# MT6631.net
KiCad netlist of a schematic drawn in Altium Designer
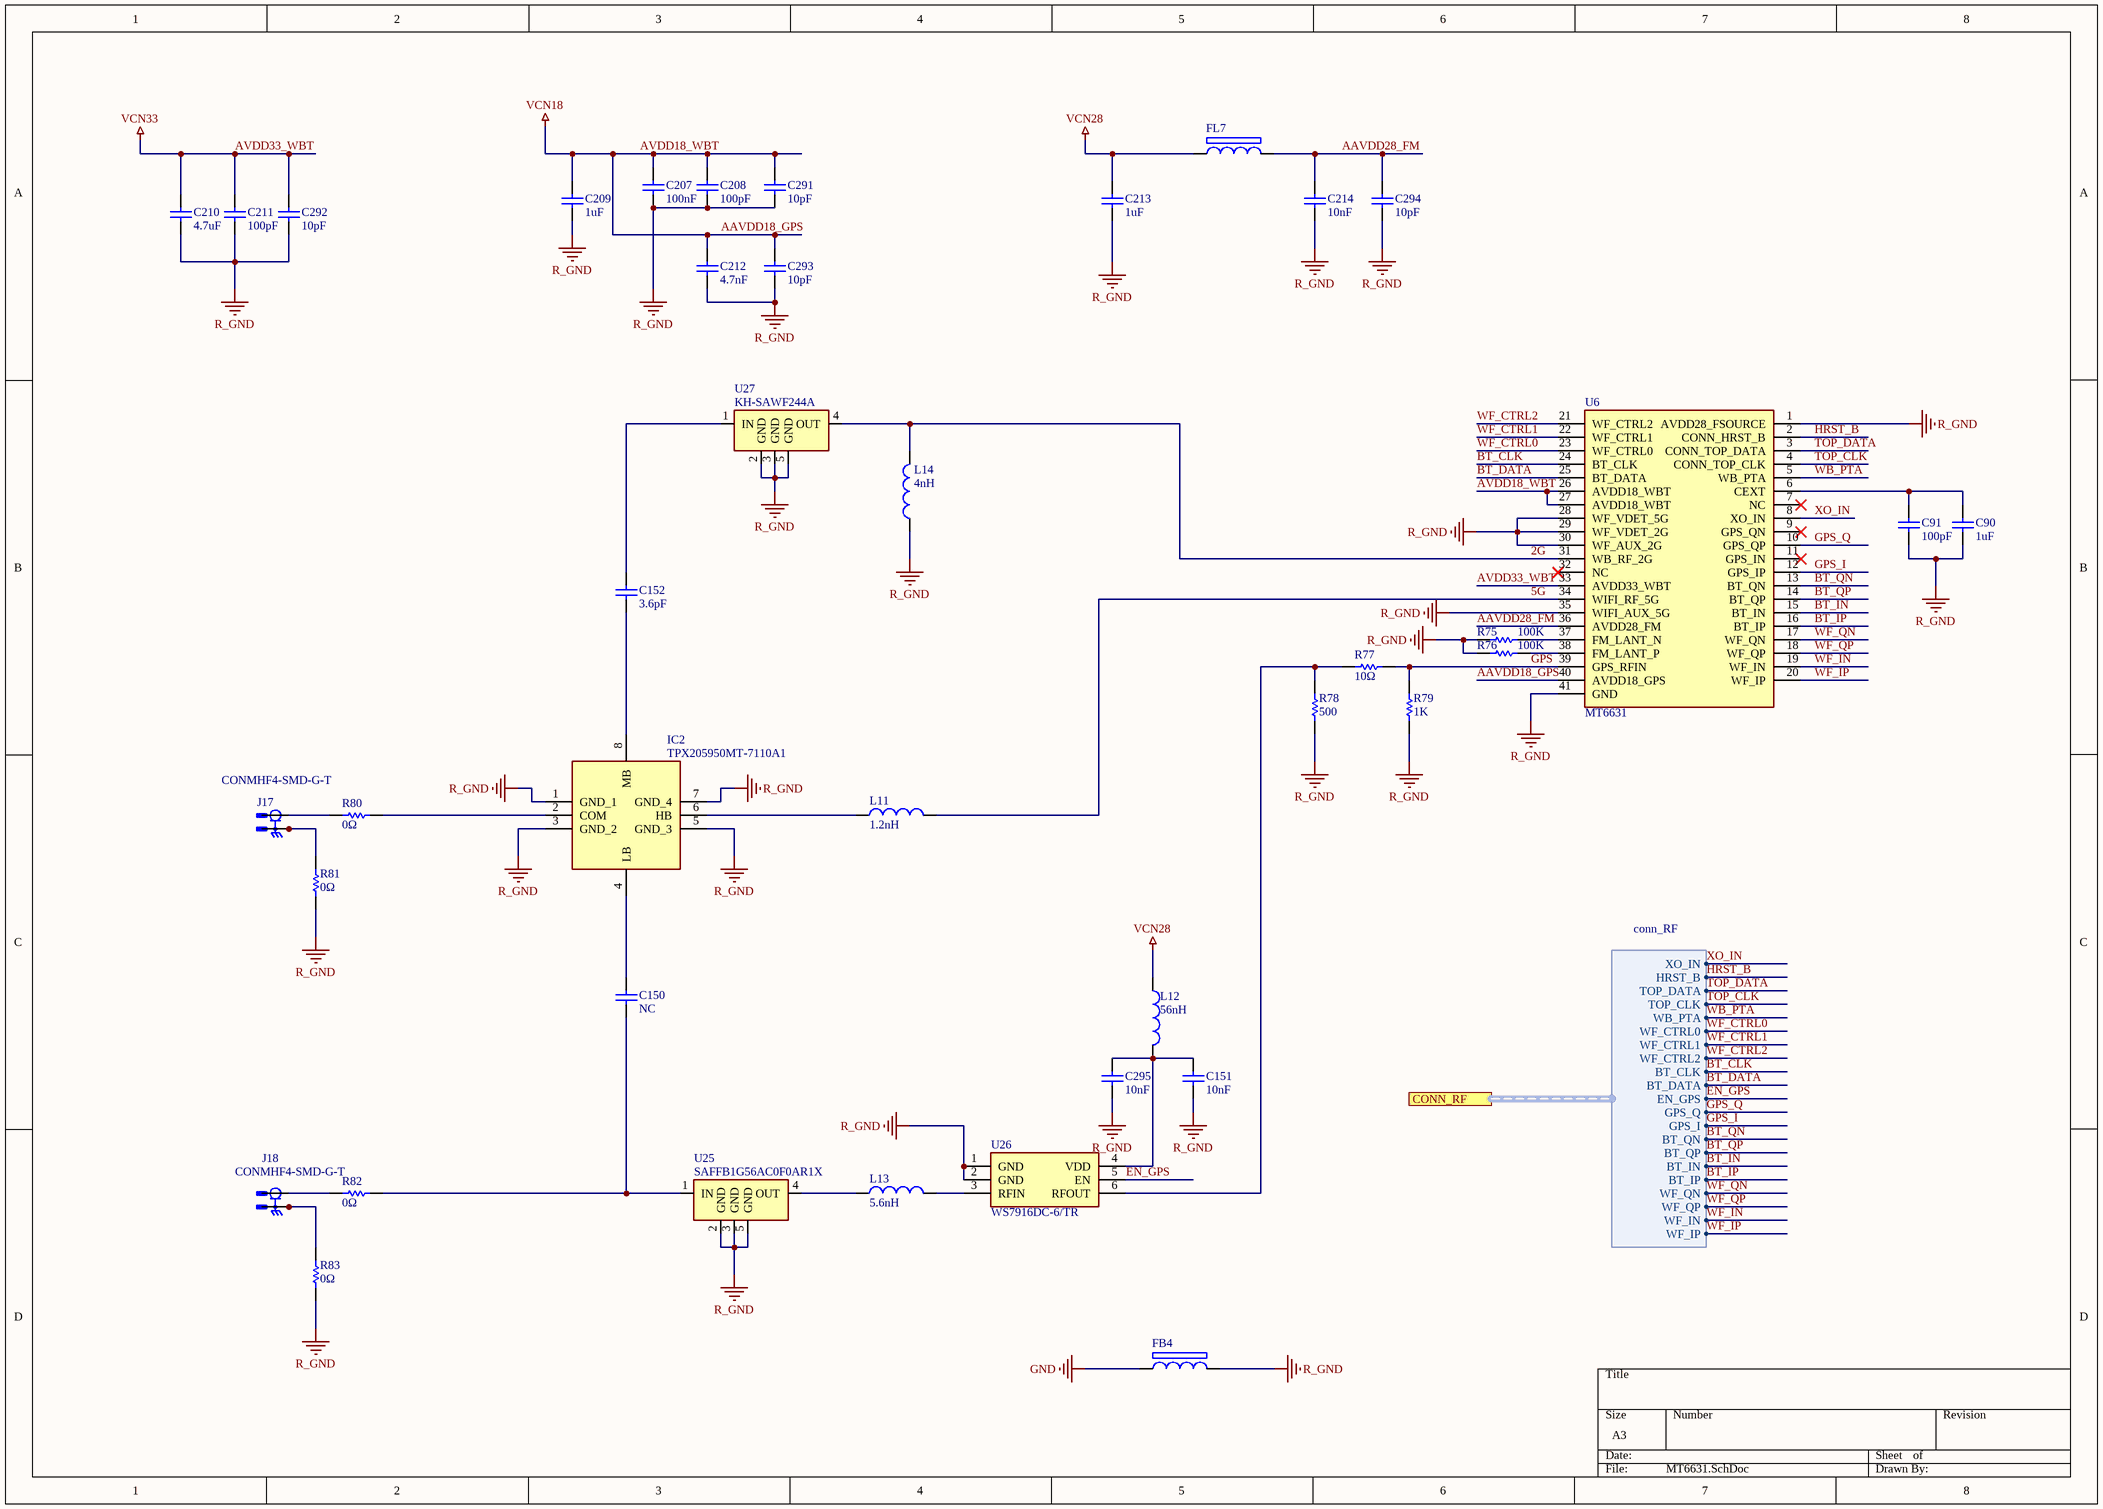
[diagram p0: MT6631.SchDoc]

(export (version "E")
  (design (tool "Eeschema 10.0.6"))
  (components
    (comp (ref "C90")
      (value "1uF")
      (footprint "C0805")
      (fields (field (name "Comment") "C0805"))
      (libsource (lib "kit") (part "C0805"))
    )
    (comp (ref "C91")
      (value "100pF")
      (footprint "C0402")
      (fields (field (name "Comment") "C0402"))
      (libsource (lib "kit") (part "C0402"))
    )
    (comp (ref "C150")
      (value "NC")
      (footprint "C0402")
      (fields (field (name "Comment") "C0402"))
      (libsource (lib "kit") (part "C0402"))
    )
    (comp (ref "C151")
      (value "10nF")
      (footprint "C0603")
      (fields (field (name "Comment") "C0603"))
      (libsource (lib "kit") (part "C0603"))
    )
    (comp (ref "C152")
      (value "3.6pF")
      (footprint "C0402")
      (fields (field (name "Comment") "C0402"))
      (libsource (lib "kit") (part "C0402"))
    )
    (comp (ref "C207")
      (value "100nF")
      (footprint "C0603")
      (fields (field (name "Comment") "C0603"))
      (libsource (lib "kit") (part "C0603"))
    )
    (comp (ref "C208")
      (value "100pF")
      (footprint "C0402")
      (fields (field (name "Comment") "C0402"))
      (libsource (lib "kit") (part "C0402"))
    )
    (comp (ref "C209")
      (value "1uF")
      (footprint "C0805")
      (fields (field (name "Comment") "C0805"))
      (libsource (lib "kit") (part "C0805"))
    )
    (comp (ref "C210")
      (value "4.7uF")
      (footprint "C0805")
      (fields (field (name "Comment") "C0805"))
      (libsource (lib "kit") (part "C0805"))
    )
    (comp (ref "C211")
      (value "100pF")
      (footprint "C0402")
      (fields (field (name "Comment") "C0402"))
      (libsource (lib "kit") (part "C0402"))
    )
    (comp (ref "C212")
      (value "4.7nF")
      (footprint "C0603")
      (fields (field (name "Comment") "C0603"))
      (libsource (lib "kit") (part "C0603"))
    )
    (comp (ref "C213")
      (value "1uF")
      (footprint "C0805")
      (fields (field (name "Comment") "C0805"))
      (libsource (lib "kit") (part "C0805"))
    )
    (comp (ref "C214")
      (value "10nF")
      (footprint "C0603")
      (fields (field (name "Comment") "C0603"))
      (libsource (lib "kit") (part "C0603"))
    )
    (comp (ref "C291")
      (value "10pF")
      (footprint "C0402")
      (fields (field (name "Comment") "C0402"))
      (libsource (lib "kit") (part "C0402"))
    )
    (comp (ref "C292")
      (value "10pF")
      (footprint "C0402")
      (fields (field (name "Comment") "C0402"))
      (libsource (lib "kit") (part "C0402"))
    )
    (comp (ref "C293")
      (value "10pF")
      (footprint "C0402")
      (fields (field (name "Comment") "C0402"))
      (libsource (lib "kit") (part "C0402"))
    )
    (comp (ref "C294")
      (value "10pF")
      (footprint "C0402")
      (fields (field (name "Comment") "C0402"))
      (libsource (lib "kit") (part "C0402"))
    )
    (comp (ref "C295")
      (value "10nF")
      (footprint "C0603")
      (fields (field (name "Comment") "C0603"))
      (libsource (lib "kit") (part "C0603"))
    )
    (comp (ref "FB4")
      (value "BLM18KG121TN1D")
      (footprint "BLM18EG101TH1D")
      (description "Ferrite Bead. 0603. 3A.  DC Resistance(DCR) 30mΩ. 120Ω@100MHz")
      (fields (field (name "MOUSER PART NUMBER") "81-BLM18KG121TN1D"))
      (libsource (lib "kit") (part "BLM18KG121TN1D"))
    )
    (comp (ref "FL7")
      (value "BLM18BD252SN1D")
      (footprint "BEADC1608X95N")
      (description "Inductor Chip Bead 2.5KOhm 25% 100MHz Ferrite 50mA 0603")
      (libsource (lib "kit") (part "BLM18BD252SN1D"))
    )
    (comp (ref "IC2")
      (value "TPX205950MT-7110A1")
      (footprint "TPX205950MT7110A1")
      (description "wifi, bluetooth, GPS. 2.4GHz, 5GHz, 1.6GHz")
      (fields (field (name "MOUSER PART NUMBER") "810-TPX20595MT7110A1"))
      (libsource (lib "kit") (part "TPX205950MT-7110A1"))
    )
    (comp (ref "J17")
      (value "CONMHF4-SMD-G-T")
      (footprint "LINX_CONMHF4-SMD-G-T")
      (description "MHF4 Jack 50 Ohm PCB Surface Mount")
      (libsource (lib "kit") (part "CONMHF4-SMD-G-T"))
    )
    (comp (ref "J18")
      (value "CONMHF4-SMD-G-T")
      (footprint "LINX_CONMHF4-SMD-G-T")
      (description "MHF4 Jack 50 Ohm PCB Surface Mount")
      (libsource (lib "kit") (part "CONMHF4-SMD-G-T"))
    )
    (comp (ref "L11")
      (value "1.2nH")
      (footprint "L0402")
      (fields (field (name "Comment") "L0402"))
      (libsource (lib "kit") (part "L0402"))
    )
    (comp (ref "L12")
      (value "56nH")
      (footprint "L0402")
      (fields (field (name "Comment") "L0402"))
      (libsource (lib "kit") (part "L0402"))
    )
    (comp (ref "L13")
      (value "5.6nH")
      (footprint "L0402")
      (fields (field (name "Comment") "L0402"))
      (libsource (lib "kit") (part "L0402"))
    )
    (comp (ref "L14")
      (value "4nH")
      (footprint "L0402")
      (fields (field (name "Comment") "L0402"))
      (libsource (lib "kit") (part "L0402"))
    )
    (comp (ref "R75")
      (value "100K")
      (footprint "R0603")
      (fields (field (name "Comment") "R0603"))
      (libsource (lib "kit") (part "R0603"))
    )
    (comp (ref "R76")
      (value "100K")
      (footprint "R0603")
      (fields (field (name "Comment") "R0603"))
      (libsource (lib "kit") (part "R0603"))
    )
    (comp (ref "R77")
      (value "10Ω")
      (footprint "R0603")
      (fields (field (name "Comment") "R0603"))
      (libsource (lib "kit") (part "R0603"))
    )
    (comp (ref "R78")
      (value "500")
      (footprint "R0603")
      (fields (field (name "Comment") "R0603"))
      (libsource (lib "kit") (part "R0603"))
    )
    (comp (ref "R79")
      (value "1K")
      (footprint "R0603")
      (fields (field (name "Comment") "R0603"))
      (libsource (lib "kit") (part "R0603"))
    )
    (comp (ref "R80")
      (value "0Ω")
      (footprint "R0603")
      (fields (field (name "Comment") "R0603"))
      (libsource (lib "kit") (part "R0603"))
    )
    (comp (ref "R81")
      (value "0Ω")
      (footprint "R0603")
      (fields (field (name "Comment") "R0603"))
      (libsource (lib "kit") (part "R0603"))
    )
    (comp (ref "R82")
      (value "0Ω")
      (footprint "R0603")
      (fields (field (name "Comment") "R0603"))
      (libsource (lib "kit") (part "R0603"))
    )
    (comp (ref "R83")
      (value "0Ω")
      (footprint "R0603")
      (fields (field (name "Comment") "R0603"))
      (libsource (lib "kit") (part "R0603"))
    )
    (comp (ref "U6") (value "MT6631") (footprint "MT6631") (libsource (lib "kit") (part "MT6631")))
    (comp (ref "U25")
      (value "SAFFB1G56AC0F0AR1X")
      (footprint "SAFFB1G56AC0F0AR1X")
      (description "lọc thông giải GPS")
      (libsource (lib "kit") (part "SAFFB1G56AC0F0AR1X"))
    )
    (comp (ref "U26")
      (value "WS7916DC-6/TR")
      (footprint "WS7916DC-6/TR")
      (description "khuếch đại tín hiệu GPS")
      (libsource (lib "kit") (part "WS7916DC-6/TR"))
    )
    (comp (ref "U27")
      (value "KH-SAWF244A")
      (footprint "KH-SAWF244A")
      (description "bộ lọc thông dải 2.4GHz")
      (libsource (lib "kit") (part "KH-SAWF244A"))
    )
  )
  (nets
    (net (code "2") (name "/2G") (class "Default")
      (node (ref "L14") (pin "2") (pinfunction "2_2") (pintype "passive"))
      (node (ref "U27") (pin "4") (pinfunction "OUT_4") (pintype "power_in"))
      (node (ref "U6") (pin "31") (pinfunction "WB_RF_2G_31") (pintype "passive"))
    )
    (net (code "3") (name "/5G") (class "Default")
      (node (ref "L11") (pin "2") (pinfunction "2_2") (pintype "passive"))
      (node (ref "U6") (pin "34") (pinfunction "WIFI_RF_5G_34") (pintype "passive"))
    )
    (net (code "4") (name "/AAVDD28_FM") (class "Default")
      (node (ref "C214") (pin "2") (pinfunction "2_2") (pintype "passive"))
      (node (ref "C294") (pin "2") (pinfunction "2_2") (pintype "passive"))
      (node (ref "FL7") (pin "2") (pinfunction "2_2") (pintype "passive"))
      (node (ref "U6") (pin "36") (pinfunction "AVDD28_FM_36") (pintype "passive"))
    )
    (net (code "5") (name "/BT_CLK") (class "Default")
      (node (ref "U6") (pin "24") (pinfunction "BT_CLK_24") (pintype "passive"))
    )
    (net (code "6") (name "/BT_DATA") (class "Default")
      (node (ref "U6") (pin "25") (pinfunction "BT_DATA_25") (pintype "passive"))
    )
    (net (code "7") (name "/BT_IN") (class "Default")
      (node (ref "U6") (pin "15") (pinfunction "BT_IN_15") (pintype "passive"))
    )
    (net (code "8") (name "/BT_IP") (class "Default")
      (node (ref "U6") (pin "16") (pinfunction "BT_IP_16") (pintype "passive"))
    )
    (net (code "9") (name "/BT_QN") (class "Default")
      (node (ref "U6") (pin "13") (pinfunction "BT_QN_13") (pintype "passive"))
    )
    (net (code "10") (name "/BT_QP") (class "Default")
      (node (ref "U6") (pin "14") (pinfunction "BT_QP_14") (pintype "passive"))
    )
    (net (code "11") (name "/EN_GPS") (class "Default")
      (node (ref "U26") (pin "5") (pinfunction "EN_5") (pintype "passive"))
    )
    (net (code "12") (name "/GPS") (class "Default")
      (node (ref "R77") (pin "2") (pinfunction "2_2") (pintype "passive"))
      (node (ref "R79") (pin "2") (pinfunction "2_2") (pintype "passive"))
      (node (ref "U6") (pin "39") (pinfunction "GPS_RFIN_39") (pintype "passive"))
    )
    (net (code "13") (name "/GPS_I") (class "Default")
      (node (ref "U6") (pin "12") (pinfunction "GPS_IP_12") (pintype "passive"))
    )
    (net (code "14") (name "/GPS_Q") (class "Default")
      (node (ref "U6") (pin "10") (pinfunction "GPS_QP_10") (pintype "passive"))
    )
    (net (code "15") (name "/HRST_B") (class "Default")
      (node (ref "U6") (pin "2") (pinfunction "CONN_HRST_B_2") (pintype "passive"))
    )
    (net (code "16") (name "/TOP_CLK") (class "Default")
      (node (ref "U6") (pin "4") (pinfunction "CONN_TOP_CLK_4") (pintype "passive"))
    )
    (net (code "17") (name "/TOP_DATA") (class "Default")
      (node (ref "U6") (pin "3") (pinfunction "CONN_TOP_DATA_3") (pintype "passive"))
    )
    (net (code "18") (name "/WB_PTA") (class "Default")
      (node (ref "U6") (pin "5") (pinfunction "WB_PTA_5") (pintype "passive"))
    )
    (net (code "19") (name "/WF_CTRL0") (class "Default")
      (node (ref "U6") (pin "23") (pinfunction "WF_CTRL0_23") (pintype "passive"))
    )
    (net (code "20") (name "/WF_CTRL1") (class "Default")
      (node (ref "U6") (pin "22") (pinfunction "WF_CTRL1_22") (pintype "passive"))
    )
    (net (code "21") (name "/WF_CTRL2") (class "Default")
      (node (ref "U6") (pin "21") (pinfunction "WF_CTRL2_21") (pintype "passive"))
    )
    (net (code "22") (name "/WF_IN") (class "Default")
      (node (ref "U6") (pin "19") (pinfunction "WF_IN_19") (pintype "passive"))
    )
    (net (code "23") (name "/WF_IP") (class "Default")
      (node (ref "U6") (pin "20") (pinfunction "WF_IP_20") (pintype "passive"))
    )
    (net (code "24") (name "/WF_QN") (class "Default")
      (node (ref "U6") (pin "17") (pinfunction "WF_QN_17") (pintype "passive"))
    )
    (net (code "25") (name "/WF_QP") (class "Default")
      (node (ref "U6") (pin "18") (pinfunction "WF_QP_18") (pintype "passive"))
    )
    (net (code "26") (name "/XO_IN") (class "Default")
      (node (ref "U6") (pin "8") (pinfunction "XO_IN_8") (pintype "passive"))
    )
    (net (code "28") (name "GND") (class "Default")
      (node (ref "FB4") (pin "1") (pinfunction "1_1") (pintype "passive"))
    )
    (net (code "29") (name "Net-(IC2-COM)") (class "Default")
      (node (ref "IC2") (pin "2") (pinfunction "COM_2") (pintype "passive"))
      (node (ref "R80") (pin "2") (pinfunction "2_2") (pintype "passive"))
    )
    (net (code "30") (name "Net-(IC2-HB)") (class "Default")
      (node (ref "IC2") (pin "6") (pinfunction "HB_6") (pintype "passive"))
      (node (ref "L11") (pin "1") (pinfunction "1_1") (pintype "passive"))
    )
    (net (code "31") (name "Net-(IC2-LB)") (class "Default")
      (node (ref "C150") (pin "2") (pinfunction "2_2") (pintype "passive"))
      (node (ref "IC2") (pin "4") (pinfunction "LB_4") (pintype "passive"))
    )
    (net (code "32") (name "Net-(IC2-MB)") (class "Default")
      (node (ref "C152") (pin "1") (pinfunction "1_1") (pintype "passive"))
      (node (ref "IC2") (pin "8") (pinfunction "MB_8") (pintype "passive"))
    )
    (net (code "33") (name "Net-(J17-2-PadS1)") (class "Default")
      (node (ref "J17") (pin "S1") (pinfunction "2_S1") (pintype "passive"))
      (node (ref "J17") (pin "S2") (pinfunction "2_S2") (pintype "passive"))
      (node (ref "J17") (pin "S3") (pinfunction "2_S3") (pintype "passive"))
      (node (ref "R81") (pin "2") (pinfunction "2_2") (pintype "passive"))
    )
    (net (code "34") (name "Net-(J17-Pad1)") (class "Default")
      (node (ref "J17") (pin "1") (pinfunction "1_1") (pintype "passive"))
      (node (ref "R80") (pin "1") (pinfunction "1_1") (pintype "passive"))
    )
    (net (code "35") (name "Net-(J18-2-PadS1)") (class "Default")
      (node (ref "J18") (pin "S1") (pinfunction "2_S1") (pintype "passive"))
      (node (ref "J18") (pin "S2") (pinfunction "2_S2") (pintype "passive"))
      (node (ref "J18") (pin "S3") (pinfunction "2_S3") (pintype "passive"))
      (node (ref "R83") (pin "2") (pinfunction "2_2") (pintype "passive"))
    )
    (net (code "36") (name "Net-(J18-Pad1)") (class "Default")
      (node (ref "J18") (pin "1") (pinfunction "1_1") (pintype "passive"))
      (node (ref "R82") (pin "1") (pinfunction "1_1") (pintype "passive"))
    )
    (net (code "37") (name "Net-(U6-CEXT)") (class "Default")
      (node (ref "C90") (pin "2") (pinfunction "2_2") (pintype "passive"))
      (node (ref "C91") (pin "2") (pinfunction "2_2") (pintype "passive"))
      (node (ref "U6") (pin "6") (pinfunction "CEXT_6") (pintype "passive"))
    )
    (net (code "38") (name "Net-(U6-FM_LANT_N)") (class "Default")
      (node (ref "R75") (pin "2") (pinfunction "2_2") (pintype "passive"))
      (node (ref "U6") (pin "37") (pinfunction "FM_LANT_N_37") (pintype "passive"))
    )
    (net (code "39") (name "Net-(U6-FM_LANT_P)") (class "Default")
      (node (ref "R76") (pin "2") (pinfunction "2_2") (pintype "passive"))
      (node (ref "U6") (pin "38") (pinfunction "FM_LANT_P_38") (pintype "passive"))
    )
    (net (code "40") (name "Net-(U25-IN)") (class "Default")
      (node (ref "C150") (pin "1") (pinfunction "1_1") (pintype "passive"))
      (node (ref "R82") (pin "2") (pinfunction "2_2") (pintype "passive"))
      (node (ref "U25") (pin "1") (pinfunction "IN_1") (pintype "power_in"))
    )
    (net (code "41") (name "Net-(U25-OUT)") (class "Default")
      (node (ref "L13") (pin "1") (pinfunction "1_1") (pintype "passive"))
      (node (ref "U25") (pin "4") (pinfunction "OUT_4") (pintype "power_in"))
    )
    (net (code "42") (name "Net-(U26-RFIN)") (class "Default")
      (node (ref "L13") (pin "2") (pinfunction "2_2") (pintype "passive"))
      (node (ref "U26") (pin "3") (pinfunction "RFIN_3") (pintype "passive"))
    )
    (net (code "43") (name "Net-(U26-RFOUT)") (class "Default")
      (node (ref "R77") (pin "1") (pinfunction "1_1") (pintype "passive"))
      (node (ref "R78") (pin "2") (pinfunction "2_2") (pintype "passive"))
      (node (ref "U26") (pin "6") (pinfunction "RFOUT_6") (pintype "passive"))
    )
    (net (code "44") (name "Net-(U26-VDD)") (class "Default")
      (node (ref "C151") (pin "2") (pinfunction "2_2") (pintype "passive"))
      (node (ref "C295") (pin "2") (pinfunction "2_2") (pintype "passive"))
      (node (ref "L12") (pin "2") (pinfunction "2_2") (pintype "passive"))
      (node (ref "U26") (pin "4") (pinfunction "VDD_4") (pintype "passive"))
    )
    (net (code "45") (name "Net-(U27-IN)") (class "Default")
      (node (ref "C152") (pin "2") (pinfunction "2_2") (pintype "passive"))
      (node (ref "U27") (pin "1") (pinfunction "IN_1") (pintype "power_in"))
    )
    (net (code "46") (name "R_GND") (class "Default")
      (node (ref "C151") (pin "1") (pinfunction "1_1") (pintype "passive"))
      (node (ref "C207") (pin "1") (pinfunction "1_1") (pintype "passive"))
      (node (ref "C208") (pin "1") (pinfunction "1_1") (pintype "passive"))
      (node (ref "C209") (pin "1") (pinfunction "1_1") (pintype "passive"))
      (node (ref "C210") (pin "1") (pinfunction "1_1") (pintype "passive"))
      (node (ref "C211") (pin "1") (pinfunction "1_1") (pintype "passive"))
      (node (ref "C212") (pin "1") (pinfunction "1_1") (pintype "passive"))
      (node (ref "C213") (pin "1") (pinfunction "1_1") (pintype "passive"))
      (node (ref "C214") (pin "1") (pinfunction "1_1") (pintype "passive"))
      (node (ref "C291") (pin "1") (pinfunction "1_1") (pintype "passive"))
      (node (ref "C292") (pin "1") (pinfunction "1_1") (pintype "passive"))
      (node (ref "C293") (pin "1") (pinfunction "1_1") (pintype "passive"))
      (node (ref "C294") (pin "1") (pinfunction "1_1") (pintype "passive"))
      (node (ref "C295") (pin "1") (pinfunction "1_1") (pintype "passive"))
      (node (ref "C90") (pin "1") (pinfunction "1_1") (pintype "passive"))
      (node (ref "C91") (pin "1") (pinfunction "1_1") (pintype "passive"))
      (node (ref "FB4") (pin "2") (pinfunction "2_2") (pintype "passive"))
      (node (ref "IC2") (pin "1") (pinfunction "GND_1_1") (pintype "passive"))
      (node (ref "IC2") (pin "3") (pinfunction "GND_2_3") (pintype "passive"))
      (node (ref "IC2") (pin "5") (pinfunction "GND_3_5") (pintype "passive"))
      (node (ref "IC2") (pin "7") (pinfunction "GND_4_7") (pintype "passive"))
      (node (ref "L14") (pin "1") (pinfunction "1_1") (pintype "passive"))
      (node (ref "R75") (pin "1") (pinfunction "1_1") (pintype "passive"))
      (node (ref "R76") (pin "1") (pinfunction "1_1") (pintype "passive"))
      (node (ref "R78") (pin "1") (pinfunction "1_1") (pintype "passive"))
      (node (ref "R79") (pin "1") (pinfunction "1_1") (pintype "passive"))
      (node (ref "R81") (pin "1") (pinfunction "1_1") (pintype "passive"))
      (node (ref "R83") (pin "1") (pinfunction "1_1") (pintype "passive"))
      (node (ref "U25") (pin "2") (pinfunction "GND_2") (pintype "power_in"))
      (node (ref "U25") (pin "3") (pinfunction "GND_3") (pintype "power_in"))
      (node (ref "U25") (pin "5") (pinfunction "GND_5") (pintype "power_in"))
      (node (ref "U26") (pin "1") (pinfunction "GND_1") (pintype "passive"))
      (node (ref "U26") (pin "2") (pinfunction "GND_2") (pintype "passive"))
      (node (ref "U27") (pin "2") (pinfunction "GND_2") (pintype "power_in"))
      (node (ref "U27") (pin "3") (pinfunction "GND_3") (pintype "power_in"))
      (node (ref "U27") (pin "5") (pinfunction "GND_5") (pintype "power_in"))
      (node (ref "U6") (pin "1") (pinfunction "AVDD28_FSOURCE_1") (pintype "passive"))
      (node (ref "U6") (pin "28") (pinfunction "WF_VDET_5G_28") (pintype "passive"))
      (node (ref "U6") (pin "29") (pinfunction "WF_VDET_2G_29") (pintype "passive"))
      (node (ref "U6") (pin "30") (pinfunction "WF_AUX_2G_30") (pintype "passive"))
      (node (ref "U6") (pin "35") (pinfunction "WIFI_AUX_5G_35") (pintype "passive"))
      (node (ref "U6") (pin "41") (pinfunction "GND_41") (pintype "passive"))
    )
    (net (code "47") (name "VCN18") (class "Default")
      (node (ref "C207") (pin "2") (pinfunction "2_2") (pintype "passive"))
      (node (ref "C208") (pin "2") (pinfunction "2_2") (pintype "passive"))
      (node (ref "C209") (pin "2") (pinfunction "2_2") (pintype "passive"))
      (node (ref "C212") (pin "2") (pinfunction "2_2") (pintype "passive"))
      (node (ref "C291") (pin "2") (pinfunction "2_2") (pintype "passive"))
      (node (ref "C293") (pin "2") (pinfunction "2_2") (pintype "passive"))
      (node (ref "U6") (pin "26") (pinfunction "AVDD18_WBT_26") (pintype "passive"))
      (node (ref "U6") (pin "27") (pinfunction "AVDD18_WBT_27") (pintype "passive"))
      (node (ref "U6") (pin "40") (pinfunction "AVDD18_GPS_40") (pintype "passive"))
    )
    (net (code "48") (name "VCN28") (class "Default")
      (node (ref "C213") (pin "2") (pinfunction "2_2") (pintype "passive"))
      (node (ref "FL7") (pin "1") (pinfunction "1_1") (pintype "passive"))
      (node (ref "L12") (pin "1") (pinfunction "1_1") (pintype "passive"))
    )
    (net (code "49") (name "VCN33") (class "Default")
      (node (ref "C210") (pin "2") (pinfunction "2_2") (pintype "passive"))
      (node (ref "C211") (pin "2") (pinfunction "2_2") (pintype "passive"))
      (node (ref "C292") (pin "2") (pinfunction "2_2") (pintype "passive"))
      (node (ref "U6") (pin "33") (pinfunction "AVDD33_WBT_33") (pintype "passive"))
    )
    (net (code "50") (name "unconnected-(U6-GPS_IN-Pad11)") (class "Default")
      (node (ref "U6") (pin "11") (pinfunction "GPS_IN_11") (pintype "passive+no_connect"))
    )
    (net (code "51") (name "unconnected-(U6-GPS_QN-Pad9)") (class "Default")
      (node (ref "U6") (pin "9") (pinfunction "GPS_QN_9") (pintype "passive+no_connect"))
    )
    (net (code "52") (name "unconnected-(U6-NC-Pad7)") (class "Default")
      (node (ref "U6") (pin "7") (pinfunction "NC_7") (pintype "passive+no_connect"))
    )
    (net (code "53") (name "unconnected-(U6-NC-Pad32)") (class "Default")
      (node (ref "U6") (pin "32") (pinfunction "NC_32") (pintype "passive+no_connect"))
    )
  )
)
